# v1_0.net
KiCad netlist of a schematic drawn in Altium Designer
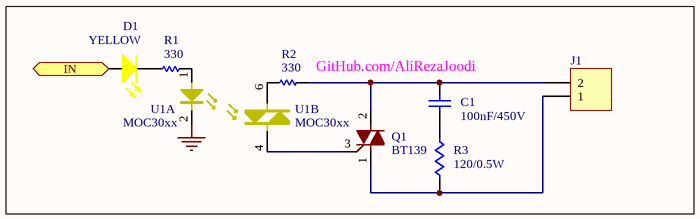
[diagram p0: v1.0.SchDoc]

(export (version "E")
  (design (tool "Eeschema 10.0.6"))
  (components
    (comp (ref "C1")
      (value "100nF/450V")
      (footprint "CAPR7.62-6.8x5")
      (description "Capacitor")
      (fields (field (name "MANUFACTURER") "Generic Components") (field (name "PUBLISHER") "Altium Limited"))
      (libsource (lib "Miscellaneous Devices") (part "Cap"))
    )
    (comp (ref "D1")
      (value "YELLOW")
      (footprint "LED_THD_3MM_YELLOW_R")
      (description "LED, Yellow")
      (fields (field (name "MANUFACTURER") "Generic Components") (field (name "PUBLISHER") "Altium Limited"))
      (libsource (lib "Display") (part "LED_YELLOW"))
    )
    (comp (ref "J1")
      (value "2PIN")
      (footprint "Fonics_2PIN_1")
      (description "Header, 2-Pin")
      (fields (field (name "PUBLISHER") "Altium Limited"))
      (libsource (lib "Miscellaneous Connectors") (part "Header 2"))
    )
    (comp (ref "Q1")
      (value "BT139")
      (footprint "TO220_3PIN_V")
      (description "Triac,")
      (libsource (lib "Passive") (part "Triac"))
    )
    (comp (ref "R1")
      (value "330")
      (footprint "R_THD_AXIAL0.4(1/4W)")
      (description "Resistor")
      (libsource (lib "Passive") (part "Resistor"))
    )
    (comp (ref "R2")
      (value "330")
      (footprint "R_THD_AXIAL0.4(1/4W)")
      (description "Resistor")
      (libsource (lib "Passive") (part "Resistor"))
    )
    (comp (ref "R3")
      (value "120/0.5W")
      (footprint "AXIAL-0.4")
      (description "Resistor")
      (fields (field (name "MANUFACTURER") "Generic Components") (field (name "PUBLISHER") "Altium Limited"))
      (libsource (lib "Miscellaneous Devices") (part "Res1"))
    )
    (comp (ref "U1")
      (value "MOC30xx")
      (footprint "DIP_6")
      (description "Opto-Triac")
      (libsource (lib "Other_Myself") (part "MOC3021"))
    )
  )
  (nets
    (net (code "1") (name "/IN") (class "Default")
      (node (ref "D1") (pin "1") (pinfunction "A_1") (pintype "passive"))
    )
    (net (code "2") (name "GND") (class "Default")
      (node (ref "U1") (pin "2") (pinfunction "K_2") (pintype "power_in"))
    )
    (net (code "3") (name "Net-(C1-Pad1)") (class "Default")
      (node (ref "C1") (pin "1") (pinfunction "1_1") (pintype "passive"))
      (node (ref "R3") (pin "2") (pinfunction "2_2") (pintype "passive"))
    )
    (net (code "4") (name "Net-(D1-K)") (class "Default")
      (node (ref "D1") (pin "2") (pinfunction "K_2") (pintype "passive"))
      (node (ref "R1") (pin "1") (pinfunction "1_1") (pintype "passive"))
    )
    (net (code "5") (name "Net-(Q1-G)") (class "Default")
      (node (ref "Q1") (pin "3") (pinfunction "G_3") (pintype "passive"))
      (node (ref "U1") (pin "4") (pinfunction "A/K_4") (pintype "passive"))
    )
    (net (code "6") (name "Net-(Q1-T1)") (class "Default")
      (node (ref "J1") (pin "1") (pinfunction "1_1") (pintype "passive"))
      (node (ref "Q1") (pin "1") (pinfunction "T1_1") (pintype "passive"))
      (node (ref "R3") (pin "1") (pinfunction "1_1") (pintype "passive"))
    )
    (net (code "7") (name "Net-(Q1-T2)") (class "Default")
      (node (ref "C1") (pin "2") (pinfunction "2_2") (pintype "passive"))
      (node (ref "J1") (pin "2") (pinfunction "2_2") (pintype "passive"))
      (node (ref "Q1") (pin "2") (pinfunction "T2_2") (pintype "passive"))
      (node (ref "R2") (pin "2") (pinfunction "2_2") (pintype "passive"))
    )
    (net (code "8") (name "Net-(R2-Pad1)") (class "Default")
      (node (ref "R2") (pin "1") (pinfunction "1_1") (pintype "passive"))
      (node (ref "U1") (pin "6") (pinfunction "A/K_6") (pintype "passive"))
    )
    (net (code "9") (name "Net-(U1A-A)") (class "Default")
      (node (ref "R1") (pin "2") (pinfunction "2_2") (pintype "passive"))
      (node (ref "U1") (pin "1") (pinfunction "A_1") (pintype "power_in"))
    )
  )
)
